# msp432_breakout_ble113.net
KiCad netlist of a schematic drawn in EAGLE
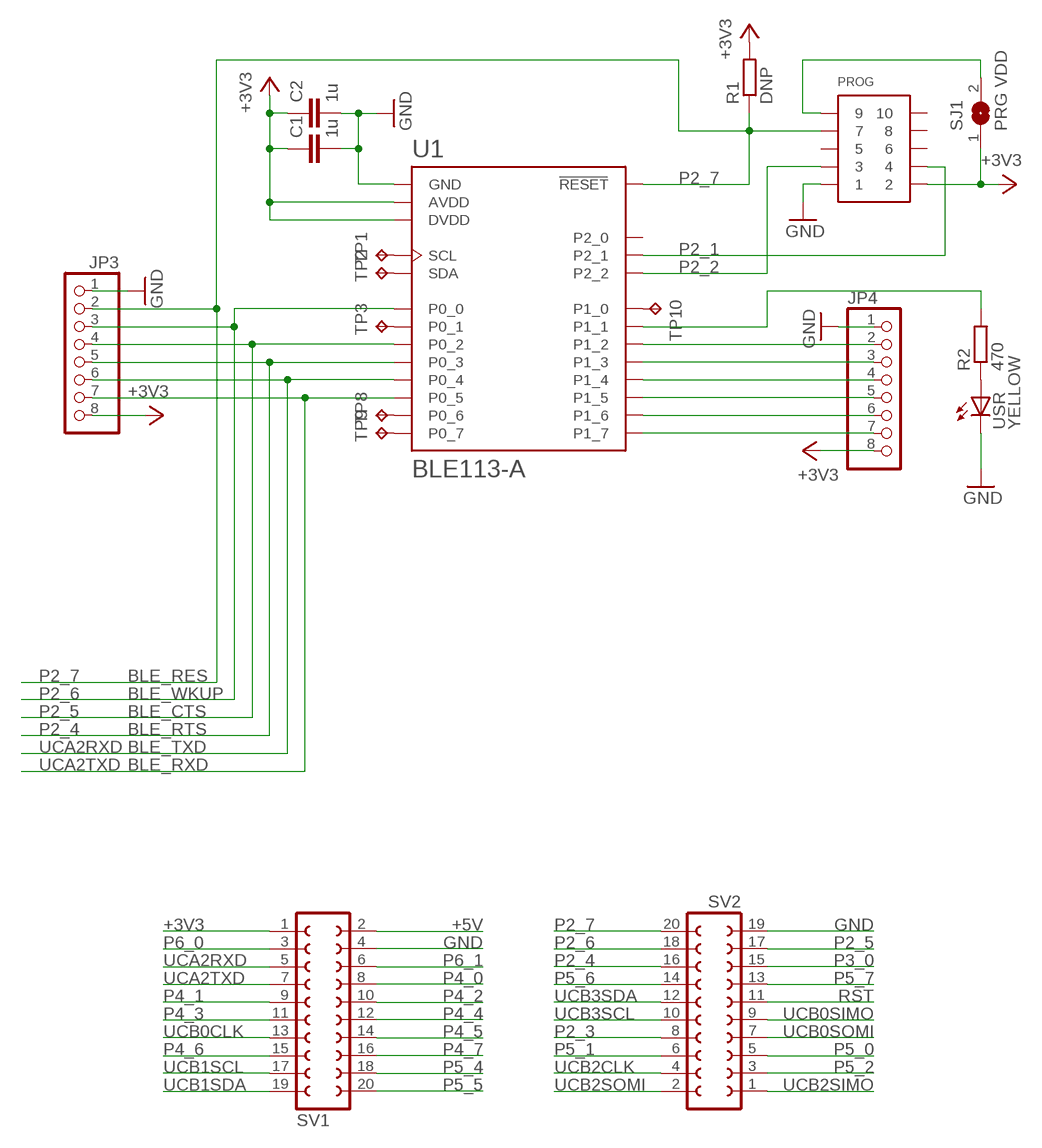
[diagram p0: schematic, sheet 1]

(export (version "E")
  (design (tool "Eeschema 10.0.6"))
  (components
    (comp (ref "C1")
      (value "1u")
      (footprint "eagle-import:C0603")
      (libsource (lib "eagle-import") (part "C-EUC0603"))
    )
    (comp (ref "C2")
      (value "1u")
      (footprint "eagle-import:C0603")
      (libsource (lib "eagle-import") (part "C-EUC0603"))
    )
    (comp (ref "JP3")
      (value "PINHD-1X8")
      (footprint "eagle-import:1X08")
      (libsource (lib "eagle-import") (part "PINHD-1X8"))
    )
    (comp (ref "JP4")
      (value "PINHD-1X8")
      (footprint "eagle-import:1X08")
      (libsource (lib "eagle-import") (part "PINHD-1X8"))
    )
    (comp (ref "PROG")
      (value "CONN_5-2-FTSH-V")
      (footprint "eagle-import:FTSH-105-DV")
      (libsource (lib "eagle-import") (part "CONN_5-2-FTSH-V"))
    )
    (comp (ref "R1")
      (value "DNP")
      (footprint "eagle-import:R0603")
      (libsource (lib "eagle-import") (part "R-EU_R0603"))
    )
    (comp (ref "R2")
      (value "470")
      (footprint "eagle-import:R0603")
      (libsource (lib "eagle-import") (part "R-EU_R0603"))
    )
    (comp (ref "SJ1")
      (value "PRG VDD")
      (footprint "eagle-import:SJ")
      (libsource (lib "eagle-import") (part "SJ"))
    )
    (comp (ref "SV1")
      (value "FE10-2")
      (footprint "eagle-import:FE10-2")
      (libsource (lib "eagle-import") (part "FE10-2"))
    )
    (comp (ref "SV2")
      (value "FE10-2")
      (footprint "eagle-import:FE10-2")
      (libsource (lib "eagle-import") (part "FE10-2"))
    )
    (comp (ref "TP1")
      (value "TPB1,27")
      (footprint "eagle-import:B1,27")
      (libsource (lib "eagle-import") (part "TPB1,27"))
    )
    (comp (ref "TP2")
      (value "TPB1,27")
      (footprint "eagle-import:B1,27")
      (libsource (lib "eagle-import") (part "TPB1,27"))
    )
    (comp (ref "TP3")
      (value "TPB1,27")
      (footprint "eagle-import:B1,27")
      (libsource (lib "eagle-import") (part "TPB1,27"))
    )
    (comp (ref "TP8")
      (value "TPB1,27")
      (footprint "eagle-import:B1,27")
      (libsource (lib "eagle-import") (part "TPB1,27"))
    )
    (comp (ref "TP9")
      (value "TPB1,27")
      (footprint "eagle-import:B1,27")
      (libsource (lib "eagle-import") (part "TPB1,27"))
    )
    (comp (ref "TP10")
      (value "TPB1,27")
      (footprint "eagle-import:B1,27")
      (libsource (lib "eagle-import") (part "TPB1,27"))
    )
    (comp (ref "U1")
      (value "BLE113-A")
      (footprint "eagle-import:BLE113-A")
      (libsource (lib "eagle-import") (part "BLE113-A"))
    )
    (comp (ref "USR")
      (value "YELLOW")
      (footprint "eagle-import:CHIPLED_0805")
      (libsource (lib "eagle-import") (part "LEDCHIPLED_0805"))
    )
  )
  (nets
    (net (code "1") (name "+3V3") (class "Default")
      (node (ref "C1") (pin "1") (pinfunction "1_1") (pintype "passive"))
      (node (ref "C2") (pin "1") (pinfunction "1_1") (pintype "passive"))
      (node (ref "JP3") (pin "8") (pinfunction "8_8") (pintype "passive"))
      (node (ref "JP4") (pin "8") (pinfunction "8_8") (pintype "passive"))
      (node (ref "PROG") (pin "2") (pinfunction "2_2") (pintype "bidirectional"))
      (node (ref "R1") (pin "2") (pinfunction "2_2") (pintype "passive"))
      (node (ref "SJ1") (pin "1") (pinfunction "1_1") (pintype "passive"))
      (node (ref "SV1") (pin "1") (pinfunction "1_1") (pintype "passive"))
      (node (ref "U1") (pin "AVDD") (pinfunction "AVDD_AVDD") (pintype "power_in"))
      (node (ref "U1") (pin "DVDD") (pinfunction "DVDD_DVDD") (pintype "power_in"))
    )
    (net (code "2") (name "/+5V") (class "Default")
      (node (ref "SV1") (pin "2") (pinfunction "2_2") (pintype "passive"))
    )
    (net (code "3") (name "/P2_1") (class "Default")
      (node (ref "PROG") (pin "4") (pinfunction "4_4") (pintype "bidirectional"))
      (node (ref "U1") (pin "P2_1") (pinfunction "P2_1_P2_1") (pintype "bidirectional"))
    )
    (net (code "4") (name "/P2_2") (class "Default")
      (node (ref "PROG") (pin "3") (pinfunction "3_3") (pintype "bidirectional"))
      (node (ref "U1") (pin "P2_2") (pinfunction "P2_2_P2_2") (pintype "bidirectional"))
    )
    (net (code "5") (name "/P2_3") (class "Default")
      (node (ref "SV2") (pin "8") (pinfunction "8_8") (pintype "passive"))
    )
    (net (code "6") (name "/P2_4") (class "Default")
      (node (ref "JP3") (pin "5") (pinfunction "5_5") (pintype "passive"))
      (node (ref "SV2") (pin "16") (pinfunction "16_16") (pintype "passive"))
      (node (ref "U1") (pin "P0_3") (pinfunction "P0_3_P0_3") (pintype "bidirectional"))
    )
    (net (code "7") (name "/P2_5") (class "Default")
      (node (ref "JP3") (pin "4") (pinfunction "4_4") (pintype "passive"))
      (node (ref "SV2") (pin "17") (pinfunction "17_17") (pintype "passive"))
      (node (ref "U1") (pin "P0_2") (pinfunction "P0_2_P0_2") (pintype "bidirectional"))
    )
    (net (code "8") (name "/P2_6") (class "Default")
      (node (ref "JP3") (pin "3") (pinfunction "3_3") (pintype "passive"))
      (node (ref "SV2") (pin "18") (pinfunction "18_18") (pintype "passive"))
      (node (ref "U1") (pin "P0_0") (pinfunction "P0_0_P0_0") (pintype "bidirectional"))
    )
    (net (code "9") (name "/P2_7") (class "Default")
      (node (ref "JP3") (pin "2") (pinfunction "2_2") (pintype "passive"))
      (node (ref "PROG") (pin "7") (pinfunction "7_7") (pintype "bidirectional"))
      (node (ref "R1") (pin "1") (pinfunction "1_1") (pintype "passive"))
      (node (ref "SV2") (pin "20") (pinfunction "20_20") (pintype "passive"))
      (node (ref "U1") (pin "RESET") (pinfunction "RESET_RESET") (pintype "input"))
    )
    (net (code "10") (name "/P3_0") (class "Default")
      (node (ref "SV2") (pin "15") (pinfunction "15_15") (pintype "passive"))
    )
    (net (code "11") (name "/P4_0") (class "Default")
      (node (ref "SV1") (pin "8") (pinfunction "8_8") (pintype "passive"))
    )
    (net (code "12") (name "/P4_1") (class "Default")
      (node (ref "SV1") (pin "9") (pinfunction "9_9") (pintype "passive"))
    )
    (net (code "13") (name "/P4_2") (class "Default")
      (node (ref "SV1") (pin "10") (pinfunction "10_10") (pintype "passive"))
    )
    (net (code "14") (name "/P4_3") (class "Default")
      (node (ref "SV1") (pin "11") (pinfunction "11_11") (pintype "passive"))
    )
    (net (code "15") (name "/P4_4") (class "Default")
      (node (ref "SV1") (pin "12") (pinfunction "12_12") (pintype "passive"))
    )
    (net (code "16") (name "/P4_5") (class "Default")
      (node (ref "SV1") (pin "14") (pinfunction "14_14") (pintype "passive"))
    )
    (net (code "17") (name "/P4_6") (class "Default")
      (node (ref "SV1") (pin "15") (pinfunction "15_15") (pintype "passive"))
    )
    (net (code "18") (name "/P4_7") (class "Default")
      (node (ref "SV1") (pin "16") (pinfunction "16_16") (pintype "passive"))
    )
    (net (code "19") (name "/P5_0") (class "Default")
      (node (ref "SV2") (pin "5") (pinfunction "5_5") (pintype "passive"))
    )
    (net (code "20") (name "/P5_1") (class "Default")
      (node (ref "SV2") (pin "6") (pinfunction "6_6") (pintype "passive"))
    )
    (net (code "21") (name "/P5_2") (class "Default")
      (node (ref "SV2") (pin "3") (pinfunction "3_3") (pintype "passive"))
    )
    (net (code "22") (name "/P5_4") (class "Default")
      (node (ref "SV1") (pin "18") (pinfunction "18_18") (pintype "passive"))
    )
    (net (code "23") (name "/P5_5") (class "Default")
      (node (ref "SV1") (pin "20") (pinfunction "20_20") (pintype "passive"))
    )
    (net (code "24") (name "/P5_6") (class "Default")
      (node (ref "SV2") (pin "14") (pinfunction "14_14") (pintype "passive"))
    )
    (net (code "25") (name "/P5_7") (class "Default")
      (node (ref "SV2") (pin "13") (pinfunction "13_13") (pintype "passive"))
    )
    (net (code "26") (name "/P6_0") (class "Default")
      (node (ref "SV1") (pin "3") (pinfunction "3_3") (pintype "passive"))
    )
    (net (code "27") (name "/P6_1") (class "Default")
      (node (ref "SV1") (pin "6") (pinfunction "6_6") (pintype "passive"))
    )
    (net (code "28") (name "/RST") (class "Default")
      (node (ref "SV2") (pin "11") (pinfunction "11_11") (pintype "passive"))
    )
    (net (code "29") (name "/UCA2RXD") (class "Default")
      (node (ref "JP3") (pin "6") (pinfunction "6_6") (pintype "passive"))
      (node (ref "SV1") (pin "5") (pinfunction "5_5") (pintype "passive"))
      (node (ref "U1") (pin "P0_4") (pinfunction "P0_4_P0_4") (pintype "bidirectional"))
    )
    (net (code "30") (name "/UCA2TXD") (class "Default")
      (node (ref "JP3") (pin "7") (pinfunction "7_7") (pintype "passive"))
      (node (ref "SV1") (pin "7") (pinfunction "7_7") (pintype "passive"))
      (node (ref "U1") (pin "P0_5") (pinfunction "P0_5_P0_5") (pintype "bidirectional"))
    )
    (net (code "31") (name "/UCB0CLK") (class "Default")
      (node (ref "SV1") (pin "13") (pinfunction "13_13") (pintype "passive"))
    )
    (net (code "32") (name "/UCB0SIMO") (class "Default")
      (node (ref "SV2") (pin "9") (pinfunction "9_9") (pintype "passive"))
    )
    (net (code "33") (name "/UCB0SOMI") (class "Default")
      (node (ref "SV2") (pin "7") (pinfunction "7_7") (pintype "passive"))
    )
    (net (code "34") (name "/UCB1SCL") (class "Default")
      (node (ref "SV1") (pin "17") (pinfunction "17_17") (pintype "passive"))
    )
    (net (code "35") (name "/UCB1SDA") (class "Default")
      (node (ref "SV1") (pin "19") (pinfunction "19_19") (pintype "passive"))
    )
    (net (code "36") (name "/UCB2CLK") (class "Default")
      (node (ref "SV2") (pin "4") (pinfunction "4_4") (pintype "passive"))
    )
    (net (code "37") (name "/UCB2SIMO") (class "Default")
      (node (ref "SV2") (pin "1") (pinfunction "1_1") (pintype "passive"))
    )
    (net (code "38") (name "/UCB2SOMI") (class "Default")
      (node (ref "SV2") (pin "2") (pinfunction "2_2") (pintype "passive"))
    )
    (net (code "39") (name "/UCB3SCL") (class "Default")
      (node (ref "SV2") (pin "10") (pinfunction "10_10") (pintype "passive"))
    )
    (net (code "40") (name "/UCB3SDA") (class "Default")
      (node (ref "SV2") (pin "12") (pinfunction "12_12") (pintype "passive"))
    )
    (net (code "41") (name "GND") (class "Default")
      (node (ref "C1") (pin "2") (pinfunction "2_2") (pintype "passive"))
      (node (ref "C2") (pin "2") (pinfunction "2_2") (pintype "passive"))
      (node (ref "JP3") (pin "1") (pinfunction "1_1") (pintype "passive"))
      (node (ref "JP4") (pin "1") (pinfunction "1_1") (pintype "passive"))
      (node (ref "PROG") (pin "1") (pinfunction "1_1") (pintype "bidirectional"))
      (node (ref "SV1") (pin "4") (pinfunction "4_4") (pintype "passive"))
      (node (ref "SV2") (pin "19") (pinfunction "19_19") (pintype "passive"))
      (node (ref "U1") (pin "GND") (pinfunction "GND_GND") (pintype "power_in"))
      (node (ref "U1") (pin "GND@10") (pinfunction "GND_GND@10") (pintype "power_in"))
      (node (ref "U1") (pin "GND@2") (pinfunction "GND_GND@2") (pintype "power_in"))
      (node (ref "U1") (pin "GND@3") (pinfunction "GND_GND@3") (pintype "power_in"))
      (node (ref "U1") (pin "GND@4") (pinfunction "GND_GND@4") (pintype "power_in"))
      (node (ref "U1") (pin "GND@5") (pinfunction "GND_GND@5") (pintype "power_in"))
      (node (ref "U1") (pin "GND@6") (pinfunction "GND_GND@6") (pintype "power_in"))
      (node (ref "U1") (pin "GND@7") (pinfunction "GND_GND@7") (pintype "power_in"))
      (node (ref "U1") (pin "GND@8") (pinfunction "GND_GND@8") (pintype "power_in"))
      (node (ref "U1") (pin "GND@9") (pinfunction "GND_GND@9") (pintype "power_in"))
      (node (ref "USR") (pin "C") (pinfunction "C_C") (pintype "passive"))
    )
    (net (code "42") (name "Net-(JP4-Pad2)") (class "Default")
      (node (ref "JP4") (pin "2") (pinfunction "2_2") (pintype "passive"))
      (node (ref "U1") (pin "P1_2") (pinfunction "P1_2_P1_2") (pintype "bidirectional"))
    )
    (net (code "43") (name "Net-(JP4-Pad3)") (class "Default")
      (node (ref "JP4") (pin "3") (pinfunction "3_3") (pintype "passive"))
      (node (ref "U1") (pin "P1_3") (pinfunction "P1_3_P1_3") (pintype "bidirectional"))
    )
    (net (code "44") (name "Net-(JP4-Pad4)") (class "Default")
      (node (ref "JP4") (pin "4") (pinfunction "4_4") (pintype "passive"))
      (node (ref "U1") (pin "P1_4") (pinfunction "P1_4_P1_4") (pintype "bidirectional"))
    )
    (net (code "45") (name "Net-(JP4-Pad5)") (class "Default")
      (node (ref "JP4") (pin "5") (pinfunction "5_5") (pintype "passive"))
      (node (ref "U1") (pin "P1_5") (pinfunction "P1_5_P1_5") (pintype "bidirectional"))
    )
    (net (code "46") (name "Net-(JP4-Pad6)") (class "Default")
      (node (ref "JP4") (pin "6") (pinfunction "6_6") (pintype "passive"))
      (node (ref "U1") (pin "P1_6") (pinfunction "P1_6_P1_6") (pintype "bidirectional"))
    )
    (net (code "47") (name "Net-(JP4-Pad7)") (class "Default")
      (node (ref "JP4") (pin "7") (pinfunction "7_7") (pintype "passive"))
      (node (ref "U1") (pin "P1_7") (pinfunction "P1_7_P1_7") (pintype "bidirectional"))
    )
    (net (code "48") (name "Net-(PROG-Pad9)") (class "Default")
      (node (ref "PROG") (pin "9") (pinfunction "9_9") (pintype "bidirectional"))
      (node (ref "SJ1") (pin "2") (pinfunction "2_2") (pintype "passive"))
    )
    (net (code "49") (name "Net-(R2-Pad1)") (class "Default")
      (node (ref "R2") (pin "1") (pinfunction "1_1") (pintype "passive"))
      (node (ref "USR") (pin "A") (pinfunction "A_A") (pintype "passive"))
    )
    (net (code "50") (name "Net-(R2-Pad2)") (class "Default")
      (node (ref "R2") (pin "2") (pinfunction "2_2") (pintype "passive"))
      (node (ref "U1") (pin "P1_1") (pinfunction "P1_1_P1_1") (pintype "bidirectional"))
    )
    (net (code "51") (name "Net-(TP1-PadTP)") (class "Default")
      (node (ref "TP1") (pin "TP") (pinfunction "TP_TP") (pintype "input"))
      (node (ref "U1") (pin "SCL") (pinfunction "SCL_SCL") (pintype "bidirectional"))
    )
    (net (code "52") (name "Net-(TP2-PadTP)") (class "Default")
      (node (ref "TP2") (pin "TP") (pinfunction "TP_TP") (pintype "input"))
      (node (ref "U1") (pin "SDA") (pinfunction "SDA_SDA") (pintype "bidirectional"))
    )
    (net (code "53") (name "Net-(TP3-PadTP)") (class "Default")
      (node (ref "TP3") (pin "TP") (pinfunction "TP_TP") (pintype "input"))
      (node (ref "U1") (pin "P0_1") (pinfunction "P0_1_P0_1") (pintype "bidirectional"))
    )
    (net (code "54") (name "Net-(TP8-PadTP)") (class "Default")
      (node (ref "TP8") (pin "TP") (pinfunction "TP_TP") (pintype "input"))
      (node (ref "U1") (pin "P0_6") (pinfunction "P0_6_P0_6") (pintype "bidirectional"))
    )
    (net (code "55") (name "Net-(TP9-PadTP)") (class "Default")
      (node (ref "TP9") (pin "TP") (pinfunction "TP_TP") (pintype "input"))
      (node (ref "U1") (pin "P0_7") (pinfunction "P0_7_P0_7") (pintype "bidirectional"))
    )
    (net (code "56") (name "Net-(TP10-PadTP)") (class "Default")
      (node (ref "TP10") (pin "TP") (pinfunction "TP_TP") (pintype "input"))
      (node (ref "U1") (pin "P1_0") (pinfunction "P1_0_P1_0") (pintype "bidirectional"))
    )
    (net (code "57") (name "unconnected-(PROG-Pad5)") (class "Default")
      (node (ref "PROG") (pin "5") (pinfunction "5_5") (pintype "bidirectional"))
    )
    (net (code "58") (name "unconnected-(PROG-Pad6)") (class "Default")
      (node (ref "PROG") (pin "6") (pinfunction "6_6") (pintype "bidirectional"))
    )
    (net (code "59") (name "unconnected-(PROG-Pad8)") (class "Default")
      (node (ref "PROG") (pin "8") (pinfunction "8_8") (pintype "bidirectional"))
    )
    (net (code "60") (name "unconnected-(PROG-Pad10)") (class "Default")
      (node (ref "PROG") (pin "10") (pinfunction "10_10") (pintype "bidirectional"))
    )
    (net (code "61") (name "unconnected-(U1-PadP2_0)") (class "Default")
      (node (ref "U1") (pin "P2_0") (pinfunction "P2_0_P2_0") (pintype "bidirectional"))
    )
  )
)
